# Pedal_LoopLEDS.net
KiCad netlist of a schematic drawn in Altium Designer
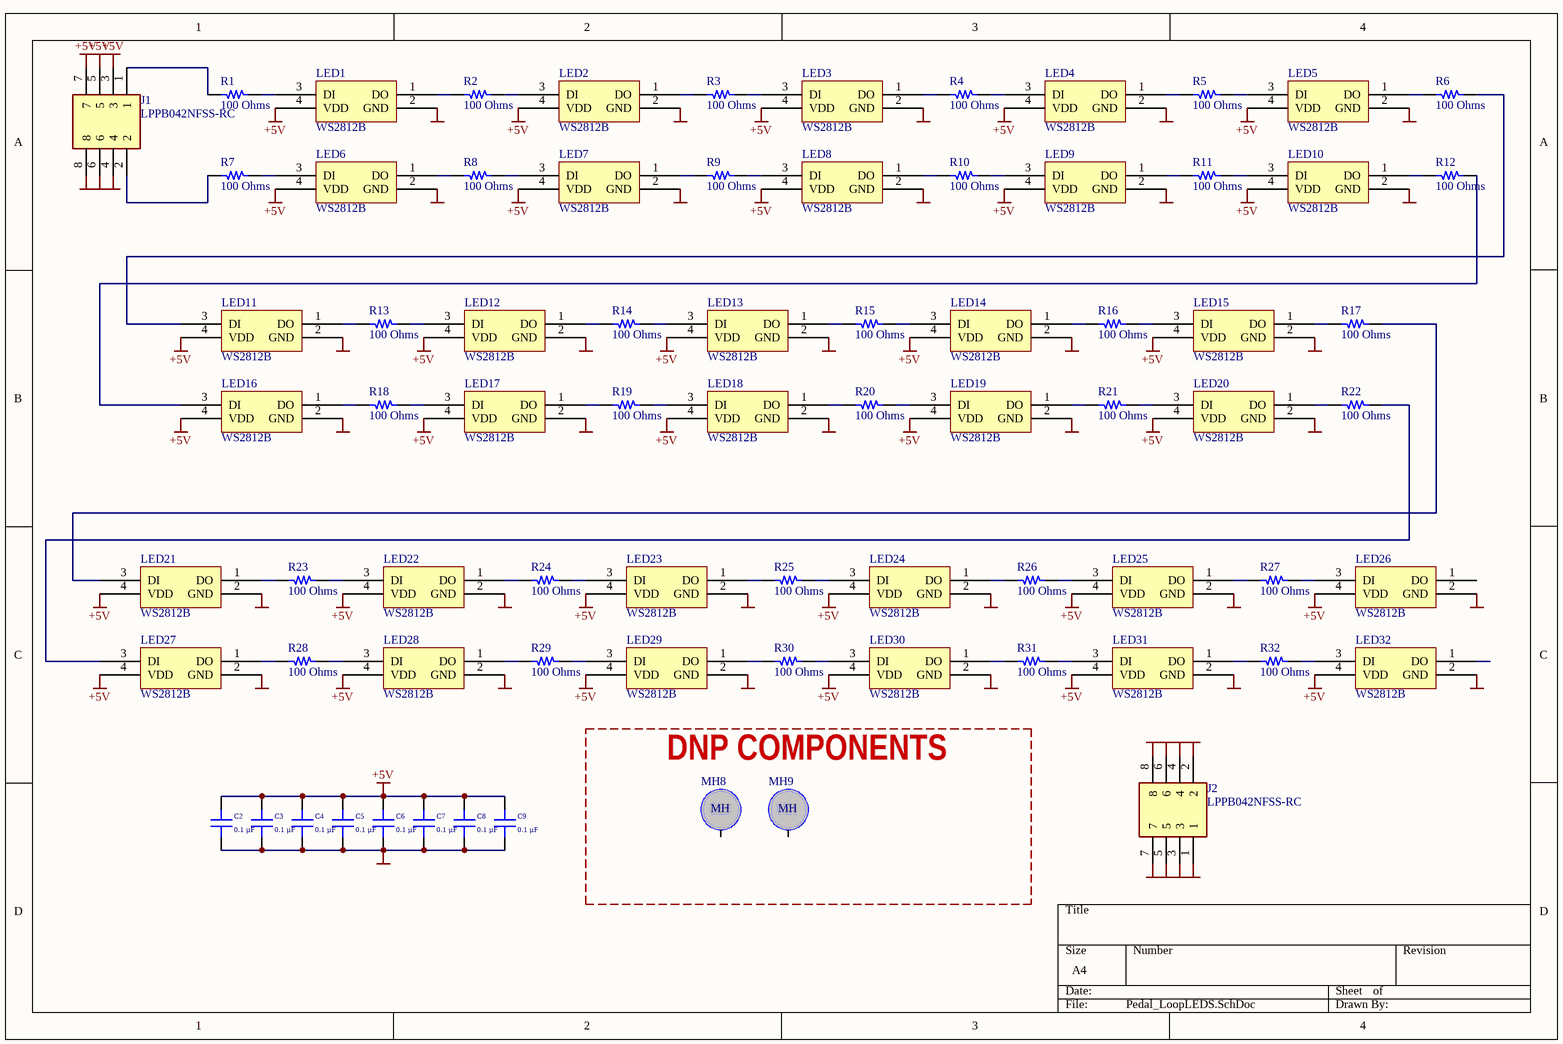
[diagram p0: Pedal_LoopLEDS.SchDoc]

(export (version "E")
  (design (tool "Eeschema 10.0.6"))
  (components
    (comp (ref "C2")
      (value "0.1 µF")
      (footprint "CAP 0603_1608")
      (description "CAP CER 0.1UF 50V X7R 0603")
      (fields (field (name "PART NUMBER") "C0603C104K5RAC7411") (field (name "MANUFACTURER") "KEMET"))
      (libsource (lib "Celestial Altium Library - altium_library") (part "Capacitor"))
    )
    (comp (ref "C3")
      (value "0.1 µF")
      (footprint "CAP 0603_1608")
      (description "CAP CER 0.1UF 50V X7R 0603")
      (fields (field (name "PART NUMBER") "C0603C104K5RAC7411") (field (name "MANUFACTURER") "KEMET"))
      (libsource (lib "Celestial Altium Library - altium_library") (part "Capacitor"))
    )
    (comp (ref "C4")
      (value "0.1 µF")
      (footprint "CAP 0603_1608")
      (description "CAP CER 0.1UF 50V X7R 0603")
      (fields (field (name "PART NUMBER") "C0603C104K5RAC7411") (field (name "MANUFACTURER") "KEMET"))
      (libsource (lib "Celestial Altium Library - altium_library") (part "Capacitor"))
    )
    (comp (ref "C5")
      (value "0.1 µF")
      (footprint "CAP 0603_1608")
      (description "CAP CER 0.1UF 50V X7R 0603")
      (fields (field (name "PART NUMBER") "C0603C104K5RAC7411") (field (name "MANUFACTURER") "KEMET"))
      (libsource (lib "Celestial Altium Library - altium_library") (part "Capacitor"))
    )
    (comp (ref "C6")
      (value "0.1 µF")
      (footprint "CAP 0603_1608")
      (description "CAP CER 0.1UF 50V X7R 0603")
      (fields (field (name "PART NUMBER") "C0603C104K5RAC7411") (field (name "MANUFACTURER") "KEMET"))
      (libsource (lib "Celestial Altium Library - altium_library") (part "Capacitor"))
    )
    (comp (ref "C7")
      (value "0.1 µF")
      (footprint "CAP 0603_1608")
      (description "CAP CER 0.1UF 50V X7R 0603")
      (fields (field (name "PART NUMBER") "C0603C104K5RAC7411") (field (name "MANUFACTURER") "KEMET"))
      (libsource (lib "Celestial Altium Library - altium_library") (part "Capacitor"))
    )
    (comp (ref "C8")
      (value "0.1 µF")
      (footprint "CAP 0603_1608")
      (description "CAP CER 0.1UF 50V X7R 0603")
      (fields (field (name "PART NUMBER") "C0603C104K5RAC7411") (field (name "MANUFACTURER") "KEMET"))
      (libsource (lib "Celestial Altium Library - altium_library") (part "Capacitor"))
    )
    (comp (ref "C9")
      (value "0.1 µF")
      (footprint "CAP 0603_1608")
      (description "CAP CER 0.1UF 50V X7R 0603")
      (fields (field (name "PART NUMBER") "C0603C104K5RAC7411") (field (name "MANUFACTURER") "KEMET"))
      (libsource (lib "Celestial Altium Library - altium_library") (part "Capacitor"))
    )
    (comp (ref "J1")
      (value "LPPB042NFSS-RC")
      (footprint "SamacSys:LPPB042NFSSRC")
      (description "Connector")
      (libsource (lib "") (part "LPPB042NFSS-RC_1"))
    )
    (comp (ref "J2")
      (value "LPPB042NFSS-RC")
      (footprint "SamacSys:LPPB042NFSSRC")
      (description "Connector")
      (libsource (lib "*") (part "LPPB042NFSS-RC"))
    )
    (comp (ref "LED1")
      (value "WS2812B")
      (footprint "ProtoStack_H750VBT:WS2812B_2.2x2mm")
      (description "Address LED")
      (libsource (lib "ProtoStack_H750VBT") (part "WS2812B"))
    )
    (comp (ref "LED2")
      (value "WS2812B")
      (footprint "ProtoStack_H750VBT:WS2812B_2.2x2mm")
      (description "Address LED")
      (libsource (lib "ProtoStack_H750VBT") (part "WS2812B"))
    )
    (comp (ref "LED3")
      (value "WS2812B")
      (footprint "ProtoStack_H750VBT:WS2812B_2.2x2mm")
      (description "Address LED")
      (libsource (lib "ProtoStack_H750VBT") (part "WS2812B"))
    )
    (comp (ref "LED4")
      (value "WS2812B")
      (footprint "ProtoStack_H750VBT:WS2812B_2.2x2mm")
      (description "Address LED")
      (libsource (lib "ProtoStack_H750VBT") (part "WS2812B"))
    )
    (comp (ref "LED5")
      (value "WS2812B")
      (footprint "ProtoStack_H750VBT:WS2812B_2.2x2mm")
      (description "Address LED")
      (libsource (lib "ProtoStack_H750VBT") (part "WS2812B"))
    )
    (comp (ref "LED6")
      (value "WS2812B")
      (footprint "ProtoStack_H750VBT:WS2812B_2.2x2mm")
      (description "Address LED")
      (libsource (lib "ProtoStack_H750VBT") (part "WS2812B"))
    )
    (comp (ref "LED7")
      (value "WS2812B")
      (footprint "ProtoStack_H750VBT:WS2812B_2.2x2mm")
      (description "Address LED")
      (libsource (lib "ProtoStack_H750VBT") (part "WS2812B"))
    )
    (comp (ref "LED8")
      (value "WS2812B")
      (footprint "ProtoStack_H750VBT:WS2812B_2.2x2mm")
      (description "Address LED")
      (libsource (lib "ProtoStack_H750VBT") (part "WS2812B"))
    )
    (comp (ref "LED9")
      (value "WS2812B")
      (footprint "ProtoStack_H750VBT:WS2812B_2.2x2mm")
      (description "Address LED")
      (libsource (lib "ProtoStack_H750VBT") (part "WS2812B"))
    )
    (comp (ref "LED10")
      (value "WS2812B")
      (footprint "ProtoStack_H750VBT:WS2812B_2.2x2mm")
      (description "Address LED")
      (libsource (lib "ProtoStack_H750VBT") (part "WS2812B"))
    )
    (comp (ref "LED11")
      (value "WS2812B")
      (footprint "ProtoStack_H750VBT:WS2812B_2.2x2mm")
      (description "Address LED")
      (libsource (lib "ProtoStack_H750VBT") (part "WS2812B"))
    )
    (comp (ref "LED12")
      (value "WS2812B")
      (footprint "ProtoStack_H750VBT:WS2812B_2.2x2mm")
      (description "Address LED")
      (libsource (lib "ProtoStack_H750VBT") (part "WS2812B"))
    )
    (comp (ref "LED13")
      (value "WS2812B")
      (footprint "ProtoStack_H750VBT:WS2812B_2.2x2mm")
      (description "Address LED")
      (libsource (lib "ProtoStack_H750VBT") (part "WS2812B"))
    )
    (comp (ref "LED14")
      (value "WS2812B")
      (footprint "ProtoStack_H750VBT:WS2812B_2.2x2mm")
      (description "Address LED")
      (libsource (lib "ProtoStack_H750VBT") (part "WS2812B"))
    )
    (comp (ref "LED15")
      (value "WS2812B")
      (footprint "ProtoStack_H750VBT:WS2812B_2.2x2mm")
      (description "Address LED")
      (libsource (lib "ProtoStack_H750VBT") (part "WS2812B"))
    )
    (comp (ref "LED16")
      (value "WS2812B")
      (footprint "ProtoStack_H750VBT:WS2812B_2.2x2mm")
      (description "Address LED")
      (libsource (lib "ProtoStack_H750VBT") (part "WS2812B"))
    )
    (comp (ref "LED17")
      (value "WS2812B")
      (footprint "ProtoStack_H750VBT:WS2812B_2.2x2mm")
      (description "Address LED")
      (libsource (lib "ProtoStack_H750VBT") (part "WS2812B"))
    )
    (comp (ref "LED18")
      (value "WS2812B")
      (footprint "ProtoStack_H750VBT:WS2812B_2.2x2mm")
      (description "Address LED")
      (libsource (lib "ProtoStack_H750VBT") (part "WS2812B"))
    )
    (comp (ref "LED19")
      (value "WS2812B")
      (footprint "ProtoStack_H750VBT:WS2812B_2.2x2mm")
      (description "Address LED")
      (libsource (lib "ProtoStack_H750VBT") (part "WS2812B"))
    )
    (comp (ref "LED20")
      (value "WS2812B")
      (footprint "ProtoStack_H750VBT:WS2812B_2.2x2mm")
      (description "Address LED")
      (libsource (lib "ProtoStack_H750VBT") (part "WS2812B"))
    )
    (comp (ref "LED21")
      (value "WS2812B")
      (footprint "ProtoStack_H750VBT:WS2812B_2.2x2mm")
      (description "Address LED")
      (libsource (lib "ProtoStack_H750VBT") (part "WS2812B"))
    )
    (comp (ref "LED22")
      (value "WS2812B")
      (footprint "ProtoStack_H750VBT:WS2812B_2.2x2mm")
      (description "Address LED")
      (libsource (lib "ProtoStack_H750VBT") (part "WS2812B"))
    )
    (comp (ref "LED23")
      (value "WS2812B")
      (footprint "ProtoStack_H750VBT:WS2812B_2.2x2mm")
      (description "Address LED")
      (libsource (lib "ProtoStack_H750VBT") (part "WS2812B"))
    )
    (comp (ref "LED24")
      (value "WS2812B")
      (footprint "ProtoStack_H750VBT:WS2812B_2.2x2mm")
      (description "Address LED")
      (libsource (lib "ProtoStack_H750VBT") (part "WS2812B"))
    )
    (comp (ref "LED25")
      (value "WS2812B")
      (footprint "ProtoStack_H750VBT:WS2812B_2.2x2mm")
      (description "Address LED")
      (libsource (lib "ProtoStack_H750VBT") (part "WS2812B"))
    )
    (comp (ref "LED26")
      (value "WS2812B")
      (footprint "ProtoStack_H750VBT:WS2812B_2.2x2mm")
      (description "Address LED")
      (libsource (lib "ProtoStack_H750VBT") (part "WS2812B"))
    )
    (comp (ref "LED27")
      (value "WS2812B")
      (footprint "ProtoStack_H750VBT:WS2812B_2.2x2mm")
      (description "Address LED")
      (libsource (lib "ProtoStack_H750VBT") (part "WS2812B"))
    )
    (comp (ref "LED28")
      (value "WS2812B")
      (footprint "ProtoStack_H750VBT:WS2812B_2.2x2mm")
      (description "Address LED")
      (libsource (lib "ProtoStack_H750VBT") (part "WS2812B"))
    )
    (comp (ref "LED29")
      (value "WS2812B")
      (footprint "ProtoStack_H750VBT:WS2812B_2.2x2mm")
      (description "Address LED")
      (libsource (lib "ProtoStack_H750VBT") (part "WS2812B"))
    )
    (comp (ref "LED30")
      (value "WS2812B")
      (footprint "ProtoStack_H750VBT:WS2812B_2.2x2mm")
      (description "Address LED")
      (libsource (lib "ProtoStack_H750VBT") (part "WS2812B"))
    )
    (comp (ref "LED31")
      (value "WS2812B")
      (footprint "ProtoStack_H750VBT:WS2812B_2.2x2mm")
      (description "Address LED")
      (libsource (lib "ProtoStack_H750VBT") (part "WS2812B"))
    )
    (comp (ref "LED32")
      (value "WS2812B")
      (footprint "ProtoStack_H750VBT:WS2812B_2.2x2mm")
      (description "Address LED")
      (libsource (lib "ProtoStack_H750VBT") (part "WS2812B"))
    )
    (comp (ref "MH8")
      (value "MountingHole")
      (footprint "ProtoStack_H750VBT:Hole_2.5mm")
      (libsource (lib "ProtoStack_H750VBT") (part "MountingHole"))
    )
    (comp (ref "MH9")
      (value "MountingHole")
      (footprint "ProtoStack_H750VBT:Hole_2.5mm")
      (libsource (lib "ProtoStack_H750VBT") (part "MountingHole"))
    )
    (comp (ref "R1")
      (value "100 Ohms")
      (footprint "RES 0402_1005")
      (description "RES SMD 100 OHM 1% 1/16W 0402")
      (fields (field (name "PART NUMBER") "CRCW0402100RFKEE") (field (name "MANUFACTURER") "Vishay Dale"))
      (libsource (lib "Celestial Altium Library - altium_library") (part "Resistor"))
    )
    (comp (ref "R2")
      (value "100 Ohms")
      (footprint "RES 0402_1005")
      (description "RES SMD 100 OHM 1% 1/16W 0402")
      (fields (field (name "PART NUMBER") "CRCW0402100RFKEE") (field (name "MANUFACTURER") "Vishay Dale"))
      (libsource (lib "Celestial Altium Library - altium_library") (part "Resistor"))
    )
    (comp (ref "R3")
      (value "100 Ohms")
      (footprint "RES 0402_1005")
      (description "RES SMD 100 OHM 1% 1/16W 0402")
      (fields (field (name "PART NUMBER") "CRCW0402100RFKEE") (field (name "MANUFACTURER") "Vishay Dale"))
      (libsource (lib "Celestial Altium Library - altium_library") (part "Resistor"))
    )
    (comp (ref "R4")
      (value "100 Ohms")
      (footprint "RES 0402_1005")
      (description "RES SMD 100 OHM 1% 1/16W 0402")
      (fields (field (name "PART NUMBER") "CRCW0402100RFKEE") (field (name "MANUFACTURER") "Vishay Dale"))
      (libsource (lib "Celestial Altium Library - altium_library") (part "Resistor"))
    )
    (comp (ref "R5")
      (value "100 Ohms")
      (footprint "RES 0402_1005")
      (description "RES SMD 100 OHM 1% 1/16W 0402")
      (fields (field (name "PART NUMBER") "CRCW0402100RFKEE") (field (name "MANUFACTURER") "Vishay Dale"))
      (libsource (lib "Celestial Altium Library - altium_library") (part "Resistor"))
    )
    (comp (ref "R6")
      (value "100 Ohms")
      (footprint "RES 0402_1005")
      (description "RES SMD 100 OHM 1% 1/16W 0402")
      (fields (field (name "PART NUMBER") "CRCW0402100RFKEE") (field (name "MANUFACTURER") "Vishay Dale"))
      (libsource (lib "Celestial Altium Library - altium_library") (part "Resistor"))
    )
    (comp (ref "R7")
      (value "100 Ohms")
      (footprint "RES 0402_1005")
      (description "RES SMD 100 OHM 1% 1/16W 0402")
      (fields (field (name "PART NUMBER") "CRCW0402100RFKEE") (field (name "MANUFACTURER") "Vishay Dale"))
      (libsource (lib "Celestial Altium Library - altium_library") (part "Resistor"))
    )
    (comp (ref "R8")
      (value "100 Ohms")
      (footprint "RES 0402_1005")
      (description "RES SMD 100 OHM 1% 1/16W 0402")
      (fields (field (name "PART NUMBER") "CRCW0402100RFKEE") (field (name "MANUFACTURER") "Vishay Dale"))
      (libsource (lib "Celestial Altium Library - altium_library") (part "Resistor"))
    )
    (comp (ref "R9")
      (value "100 Ohms")
      (footprint "RES 0402_1005")
      (description "RES SMD 100 OHM 1% 1/16W 0402")
      (fields (field (name "PART NUMBER") "CRCW0402100RFKEE") (field (name "MANUFACTURER") "Vishay Dale"))
      (libsource (lib "Celestial Altium Library - altium_library") (part "Resistor"))
    )
    (comp (ref "R10")
      (value "100 Ohms")
      (footprint "RES 0402_1005")
      (description "RES SMD 100 OHM 1% 1/16W 0402")
      (fields (field (name "PART NUMBER") "CRCW0402100RFKEE") (field (name "MANUFACTURER") "Vishay Dale"))
      (libsource (lib "Celestial Altium Library - altium_library") (part "Resistor"))
    )
    (comp (ref "R11")
      (value "100 Ohms")
      (footprint "RES 0402_1005")
      (description "RES SMD 100 OHM 1% 1/16W 0402")
      (fields (field (name "PART NUMBER") "CRCW0402100RFKEE") (field (name "MANUFACTURER") "Vishay Dale"))
      (libsource (lib "Celestial Altium Library - altium_library") (part "Resistor"))
    )
    (comp (ref "R12")
      (value "100 Ohms")
      (footprint "RES 0402_1005")
      (description "RES SMD 100 OHM 1% 1/16W 0402")
      (fields (field (name "PART NUMBER") "CRCW0402100RFKEE") (field (name "MANUFACTURER") "Vishay Dale"))
      (libsource (lib "Celestial Altium Library - altium_library") (part "Resistor"))
    )
    (comp (ref "R13")
      (value "100 Ohms")
      (footprint "RES 0402_1005")
      (description "RES SMD 100 OHM 1% 1/16W 0402")
      (fields (field (name "PART NUMBER") "CRCW0402100RFKEE") (field (name "MANUFACTURER") "Vishay Dale"))
      (libsource (lib "Celestial Altium Library - altium_library") (part "Resistor"))
    )
    (comp (ref "R14")
      (value "100 Ohms")
      (footprint "RES 0402_1005")
      (description "RES SMD 100 OHM 1% 1/16W 0402")
      (fields (field (name "PART NUMBER") "CRCW0402100RFKEE") (field (name "MANUFACTURER") "Vishay Dale"))
      (libsource (lib "Celestial Altium Library - altium_library") (part "Resistor"))
    )
    (comp (ref "R15")
      (value "100 Ohms")
      (footprint "RES 0402_1005")
      (description "RES SMD 100 OHM 1% 1/16W 0402")
      (fields (field (name "PART NUMBER") "CRCW0402100RFKEE") (field (name "MANUFACTURER") "Vishay Dale"))
      (libsource (lib "Celestial Altium Library - altium_library") (part "Resistor"))
    )
    (comp (ref "R16")
      (value "100 Ohms")
      (footprint "RES 0402_1005")
      (description "RES SMD 100 OHM 1% 1/16W 0402")
      (fields (field (name "PART NUMBER") "CRCW0402100RFKEE") (field (name "MANUFACTURER") "Vishay Dale"))
      (libsource (lib "Celestial Altium Library - altium_library") (part "Resistor"))
    )
    (comp (ref "R17")
      (value "100 Ohms")
      (footprint "RES 0402_1005")
      (description "RES SMD 100 OHM 1% 1/16W 0402")
      (fields (field (name "PART NUMBER") "CRCW0402100RFKEE") (field (name "MANUFACTURER") "Vishay Dale"))
      (libsource (lib "Celestial Altium Library - altium_library") (part "Resistor"))
    )
    (comp (ref "R18")
      (value "100 Ohms")
      (footprint "RES 0402_1005")
      (description "RES SMD 100 OHM 1% 1/16W 0402")
      (fields (field (name "PART NUMBER") "CRCW0402100RFKEE") (field (name "MANUFACTURER") "Vishay Dale"))
      (libsource (lib "Celestial Altium Library - altium_library") (part "Resistor"))
    )
    (comp (ref "R19")
      (value "100 Ohms")
      (footprint "RES 0402_1005")
      (description "RES SMD 100 OHM 1% 1/16W 0402")
      (fields (field (name "PART NUMBER") "CRCW0402100RFKEE") (field (name "MANUFACTURER") "Vishay Dale"))
      (libsource (lib "Celestial Altium Library - altium_library") (part "Resistor"))
    )
    (comp (ref "R20")
      (value "100 Ohms")
      (footprint "RES 0402_1005")
      (description "RES SMD 100 OHM 1% 1/16W 0402")
      (fields (field (name "PART NUMBER") "CRCW0402100RFKEE") (field (name "MANUFACTURER") "Vishay Dale"))
      (libsource (lib "Celestial Altium Library - altium_library") (part "Resistor"))
    )
    (comp (ref "R21")
      (value "100 Ohms")
      (footprint "RES 0402_1005")
      (description "RES SMD 100 OHM 1% 1/16W 0402")
      (fields (field (name "PART NUMBER") "CRCW0402100RFKEE") (field (name "MANUFACTURER") "Vishay Dale"))
      (libsource (lib "Celestial Altium Library - altium_library") (part "Resistor"))
    )
    (comp (ref "R22")
      (value "100 Ohms")
      (footprint "RES 0402_1005")
      (description "RES SMD 100 OHM 1% 1/16W 0402")
      (fields (field (name "PART NUMBER") "CRCW0402100RFKEE") (field (name "MANUFACTURER") "Vishay Dale"))
      (libsource (lib "Celestial Altium Library - altium_library") (part "Resistor"))
    )
    (comp (ref "R23")
      (value "100 Ohms")
      (footprint "RES 0402_1005")
      (description "RES SMD 100 OHM 1% 1/16W 0402")
      (fields (field (name "PART NUMBER") "CRCW0402100RFKEE") (field (name "MANUFACTURER") "Vishay Dale"))
      (libsource (lib "Celestial Altium Library - altium_library") (part "Resistor"))
    )
    (comp (ref "R24")
      (value "100 Ohms")
      (footprint "RES 0402_1005")
      (description "RES SMD 100 OHM 1% 1/16W 0402")
      (fields (field (name "PART NUMBER") "CRCW0402100RFKEE") (field (name "MANUFACTURER") "Vishay Dale"))
      (libsource (lib "Celestial Altium Library - altium_library") (part "Resistor"))
    )
    (comp (ref "R25")
      (value "100 Ohms")
      (footprint "RES 0402_1005")
      (description "RES SMD 100 OHM 1% 1/16W 0402")
      (fields (field (name "PART NUMBER") "CRCW0402100RFKEE") (field (name "MANUFACTURER") "Vishay Dale"))
      (libsource (lib "Celestial Altium Library - altium_library") (part "Resistor"))
    )
    (comp (ref "R26")
      (value "100 Ohms")
      (footprint "RES 0402_1005")
      (description "RES SMD 100 OHM 1% 1/16W 0402")
      (fields (field (name "PART NUMBER") "CRCW0402100RFKEE") (field (name "MANUFACTURER") "Vishay Dale"))
      (libsource (lib "Celestial Altium Library - altium_library") (part "Resistor"))
    )
    (comp (ref "R27")
      (value "100 Ohms")
      (footprint "RES 0402_1005")
      (description "RES SMD 100 OHM 1% 1/16W 0402")
      (fields (field (name "PART NUMBER") "CRCW0402100RFKEE") (field (name "MANUFACTURER") "Vishay Dale"))
      (libsource (lib "Celestial Altium Library - altium_library") (part "Resistor"))
    )
    (comp (ref "R28")
      (value "100 Ohms")
      (footprint "RES 0402_1005")
      (description "RES SMD 100 OHM 1% 1/16W 0402")
      (fields (field (name "PART NUMBER") "CRCW0402100RFKEE") (field (name "MANUFACTURER") "Vishay Dale"))
      (libsource (lib "Celestial Altium Library - altium_library") (part "Resistor"))
    )
    (comp (ref "R29")
      (value "100 Ohms")
      (footprint "RES 0402_1005")
      (description "RES SMD 100 OHM 1% 1/16W 0402")
      (fields (field (name "PART NUMBER") "CRCW0402100RFKEE") (field (name "MANUFACTURER") "Vishay Dale"))
      (libsource (lib "Celestial Altium Library - altium_library") (part "Resistor"))
    )
    (comp (ref "R30")
      (value "100 Ohms")
      (footprint "RES 0402_1005")
      (description "RES SMD 100 OHM 1% 1/16W 0402")
      (fields (field (name "PART NUMBER") "CRCW0402100RFKEE") (field (name "MANUFACTURER") "Vishay Dale"))
      (libsource (lib "Celestial Altium Library - altium_library") (part "Resistor"))
    )
    (comp (ref "R31")
      (value "100 Ohms")
      (footprint "RES 0402_1005")
      (description "RES SMD 100 OHM 1% 1/16W 0402")
      (fields (field (name "PART NUMBER") "CRCW0402100RFKEE") (field (name "MANUFACTURER") "Vishay Dale"))
      (libsource (lib "Celestial Altium Library - altium_library") (part "Resistor"))
    )
    (comp (ref "R32")
      (value "100 Ohms")
      (footprint "RES 0402_1005")
      (description "RES SMD 100 OHM 1% 1/16W 0402")
      (fields (field (name "PART NUMBER") "CRCW0402100RFKEE") (field (name "MANUFACTURER") "Vishay Dale"))
      (libsource (lib "Celestial Altium Library - altium_library") (part "Resistor"))
    )
  )
  (nets
    (net (code "1") (name "+5V") (class "Default")
      (node (ref "C2") (pin "2") (pinfunction "2_2") (pintype "passive"))
      (node (ref "C3") (pin "2") (pinfunction "2_2") (pintype "passive"))
      (node (ref "C4") (pin "2") (pinfunction "2_2") (pintype "passive"))
      (node (ref "C5") (pin "2") (pinfunction "2_2") (pintype "passive"))
      (node (ref "C6") (pin "2") (pinfunction "2_2") (pintype "passive"))
      (node (ref "C7") (pin "2") (pinfunction "2_2") (pintype "passive"))
      (node (ref "C8") (pin "2") (pinfunction "2_2") (pintype "passive"))
      (node (ref "C9") (pin "2") (pinfunction "2_2") (pintype "passive"))
      (node (ref "J1") (pin "3") (pinfunction "3_3") (pintype "passive"))
      (node (ref "J1") (pin "5") (pinfunction "5_5") (pintype "passive"))
      (node (ref "J1") (pin "7") (pinfunction "7_7") (pintype "passive"))
      (node (ref "LED1") (pin "4") (pinfunction "VDD_4") (pintype "passive"))
      (node (ref "LED10") (pin "4") (pinfunction "VDD_4") (pintype "passive"))
      (node (ref "LED11") (pin "4") (pinfunction "VDD_4") (pintype "passive"))
      (node (ref "LED12") (pin "4") (pinfunction "VDD_4") (pintype "passive"))
      (node (ref "LED13") (pin "4") (pinfunction "VDD_4") (pintype "passive"))
      (node (ref "LED14") (pin "4") (pinfunction "VDD_4") (pintype "passive"))
      (node (ref "LED15") (pin "4") (pinfunction "VDD_4") (pintype "passive"))
      (node (ref "LED16") (pin "4") (pinfunction "VDD_4") (pintype "passive"))
      (node (ref "LED17") (pin "4") (pinfunction "VDD_4") (pintype "passive"))
      (node (ref "LED18") (pin "4") (pinfunction "VDD_4") (pintype "passive"))
      (node (ref "LED19") (pin "4") (pinfunction "VDD_4") (pintype "passive"))
      (node (ref "LED2") (pin "4") (pinfunction "VDD_4") (pintype "passive"))
      (node (ref "LED20") (pin "4") (pinfunction "VDD_4") (pintype "passive"))
      (node (ref "LED21") (pin "4") (pinfunction "VDD_4") (pintype "passive"))
      (node (ref "LED22") (pin "4") (pinfunction "VDD_4") (pintype "passive"))
      (node (ref "LED23") (pin "4") (pinfunction "VDD_4") (pintype "passive"))
      (node (ref "LED24") (pin "4") (pinfunction "VDD_4") (pintype "passive"))
      (node (ref "LED25") (pin "4") (pinfunction "VDD_4") (pintype "passive"))
      (node (ref "LED26") (pin "4") (pinfunction "VDD_4") (pintype "passive"))
      (node (ref "LED27") (pin "4") (pinfunction "VDD_4") (pintype "passive"))
      (node (ref "LED28") (pin "4") (pinfunction "VDD_4") (pintype "passive"))
      (node (ref "LED29") (pin "4") (pinfunction "VDD_4") (pintype "passive"))
      (node (ref "LED3") (pin "4") (pinfunction "VDD_4") (pintype "passive"))
      (node (ref "LED30") (pin "4") (pinfunction "VDD_4") (pintype "passive"))
      (node (ref "LED31") (pin "4") (pinfunction "VDD_4") (pintype "passive"))
      (node (ref "LED32") (pin "4") (pinfunction "VDD_4") (pintype "passive"))
      (node (ref "LED4") (pin "4") (pinfunction "VDD_4") (pintype "passive"))
      (node (ref "LED5") (pin "4") (pinfunction "VDD_4") (pintype "passive"))
      (node (ref "LED6") (pin "4") (pinfunction "VDD_4") (pintype "passive"))
      (node (ref "LED7") (pin "4") (pinfunction "VDD_4") (pintype "passive"))
      (node (ref "LED8") (pin "4") (pinfunction "VDD_4") (pintype "passive"))
      (node (ref "LED9") (pin "4") (pinfunction "VDD_4") (pintype "passive"))
    )
    (net (code "2") (name "GND") (class "Default")
      (node (ref "C2") (pin "1") (pinfunction "1_1") (pintype "passive"))
      (node (ref "C3") (pin "1") (pinfunction "1_1") (pintype "passive"))
      (node (ref "C4") (pin "1") (pinfunction "1_1") (pintype "passive"))
      (node (ref "C5") (pin "1") (pinfunction "1_1") (pintype "passive"))
      (node (ref "C6") (pin "1") (pinfunction "1_1") (pintype "passive"))
      (node (ref "C7") (pin "1") (pinfunction "1_1") (pintype "passive"))
      (node (ref "C8") (pin "1") (pinfunction "1_1") (pintype "passive"))
      (node (ref "C9") (pin "1") (pinfunction "1_1") (pintype "passive"))
      (node (ref "J1") (pin "4") (pinfunction "4_4") (pintype "passive"))
      (node (ref "J1") (pin "6") (pinfunction "6_6") (pintype "passive"))
      (node (ref "J1") (pin "8") (pinfunction "8_8") (pintype "passive"))
      (node (ref "J2") (pin "1") (pinfunction "1_1") (pintype "passive"))
      (node (ref "J2") (pin "2") (pinfunction "2_2") (pintype "passive"))
      (node (ref "J2") (pin "3") (pinfunction "3_3") (pintype "passive"))
      (node (ref "J2") (pin "4") (pinfunction "4_4") (pintype "passive"))
      (node (ref "J2") (pin "5") (pinfunction "5_5") (pintype "passive"))
      (node (ref "J2") (pin "6") (pinfunction "6_6") (pintype "passive"))
      (node (ref "J2") (pin "7") (pinfunction "7_7") (pintype "passive"))
      (node (ref "J2") (pin "8") (pinfunction "8_8") (pintype "passive"))
      (node (ref "LED1") (pin "2") (pinfunction "GND_2") (pintype "passive"))
      (node (ref "LED10") (pin "2") (pinfunction "GND_2") (pintype "passive"))
      (node (ref "LED11") (pin "2") (pinfunction "GND_2") (pintype "passive"))
      (node (ref "LED12") (pin "2") (pinfunction "GND_2") (pintype "passive"))
      (node (ref "LED13") (pin "2") (pinfunction "GND_2") (pintype "passive"))
      (node (ref "LED14") (pin "2") (pinfunction "GND_2") (pintype "passive"))
      (node (ref "LED15") (pin "2") (pinfunction "GND_2") (pintype "passive"))
      (node (ref "LED16") (pin "2") (pinfunction "GND_2") (pintype "passive"))
      (node (ref "LED17") (pin "2") (pinfunction "GND_2") (pintype "passive"))
      (node (ref "LED18") (pin "2") (pinfunction "GND_2") (pintype "passive"))
      (node (ref "LED19") (pin "2") (pinfunction "GND_2") (pintype "passive"))
      (node (ref "LED2") (pin "2") (pinfunction "GND_2") (pintype "passive"))
      (node (ref "LED20") (pin "2") (pinfunction "GND_2") (pintype "passive"))
      (node (ref "LED21") (pin "2") (pinfunction "GND_2") (pintype "passive"))
      (node (ref "LED22") (pin "2") (pinfunction "GND_2") (pintype "passive"))
      (node (ref "LED23") (pin "2") (pinfunction "GND_2") (pintype "passive"))
      (node (ref "LED24") (pin "2") (pinfunction "GND_2") (pintype "passive"))
      (node (ref "LED25") (pin "2") (pinfunction "GND_2") (pintype "passive"))
      (node (ref "LED26") (pin "2") (pinfunction "GND_2") (pintype "passive"))
      (node (ref "LED27") (pin "2") (pinfunction "GND_2") (pintype "passive"))
      (node (ref "LED28") (pin "2") (pinfunction "GND_2") (pintype "passive"))
      (node (ref "LED29") (pin "2") (pinfunction "GND_2") (pintype "passive"))
      (node (ref "LED3") (pin "2") (pinfunction "GND_2") (pintype "passive"))
      (node (ref "LED30") (pin "2") (pinfunction "GND_2") (pintype "passive"))
      (node (ref "LED31") (pin "2") (pinfunction "GND_2") (pintype "passive"))
      (node (ref "LED32") (pin "2") (pinfunction "GND_2") (pintype "passive"))
      (node (ref "LED4") (pin "2") (pinfunction "GND_2") (pintype "passive"))
      (node (ref "LED5") (pin "2") (pinfunction "GND_2") (pintype "passive"))
      (node (ref "LED6") (pin "2") (pinfunction "GND_2") (pintype "passive"))
      (node (ref "LED7") (pin "2") (pinfunction "GND_2") (pintype "passive"))
      (node (ref "LED8") (pin "2") (pinfunction "GND_2") (pintype "passive"))
      (node (ref "LED9") (pin "2") (pinfunction "GND_2") (pintype "passive"))
    )
    (net (code "3") (name "Net-(J1-Pad1)") (class "Default")
      (node (ref "J1") (pin "1") (pinfunction "1_1") (pintype "passive"))
      (node (ref "R1") (pin "2") (pinfunction "2_2") (pintype "passive"))
    )
    (net (code "4") (name "Net-(J1-Pad2)") (class "Default")
      (node (ref "J1") (pin "2") (pinfunction "2_2") (pintype "passive"))
      (node (ref "R7") (pin "2") (pinfunction "2_2") (pintype "passive"))
    )
    (net (code "5") (name "Net-(LED1-DI)") (class "Default")
      (node (ref "LED1") (pin "3") (pinfunction "DI_3") (pintype "passive"))
      (node (ref "R1") (pin "1") (pinfunction "1_1") (pintype "passive"))
    )
    (net (code "6") (name "Net-(LED1-DO)") (class "Default")
      (node (ref "LED1") (pin "1") (pinfunction "DO_1") (pintype "passive"))
      (node (ref "R2") (pin "2") (pinfunction "2_2") (pintype "passive"))
    )
    (net (code "7") (name "Net-(LED2-DI)") (class "Default")
      (node (ref "LED2") (pin "3") (pinfunction "DI_3") (pintype "passive"))
      (node (ref "R2") (pin "1") (pinfunction "1_1") (pintype "passive"))
    )
    (net (code "8") (name "Net-(LED2-DO)") (class "Default")
      (node (ref "LED2") (pin "1") (pinfunction "DO_1") (pintype "passive"))
      (node (ref "R3") (pin "2") (pinfunction "2_2") (pintype "passive"))
    )
    (net (code "9") (name "Net-(LED3-DI)") (class "Default")
      (node (ref "LED3") (pin "3") (pinfunction "DI_3") (pintype "passive"))
      (node (ref "R3") (pin "1") (pinfunction "1_1") (pintype "passive"))
    )
    (net (code "10") (name "Net-(LED3-DO)") (class "Default")
      (node (ref "LED3") (pin "1") (pinfunction "DO_1") (pintype "passive"))
      (node (ref "R4") (pin "2") (pinfunction "2_2") (pintype "passive"))
    )
    (net (code "11") (name "Net-(LED4-DI)") (class "Default")
      (node (ref "LED4") (pin "3") (pinfunction "DI_3") (pintype "passive"))
      (node (ref "R4") (pin "1") (pinfunction "1_1") (pintype "passive"))
    )
    (net (code "12") (name "Net-(LED4-DO)") (class "Default")
      (node (ref "LED4") (pin "1") (pinfunction "DO_1") (pintype "passive"))
      (node (ref "R5") (pin "2") (pinfunction "2_2") (pintype "passive"))
    )
    (net (code "13") (name "Net-(LED5-DI)") (class "Default")
      (node (ref "LED5") (pin "3") (pinfunction "DI_3") (pintype "passive"))
      (node (ref "R5") (pin "1") (pinfunction "1_1") (pintype "passive"))
    )
    (net (code "14") (name "Net-(LED5-DO)") (class "Default")
      (node (ref "LED5") (pin "1") (pinfunction "DO_1") (pintype "passive"))
      (node (ref "R6") (pin "2") (pinfunction "2_2") (pintype "passive"))
    )
    (net (code "15") (name "Net-(LED6-DI)") (class "Default")
      (node (ref "LED6") (pin "3") (pinfunction "DI_3") (pintype "passive"))
      (node (ref "R7") (pin "1") (pinfunction "1_1") (pintype "passive"))
    )
    (net (code "16") (name "Net-(LED6-DO)") (class "Default")
      (node (ref "LED6") (pin "1") (pinfunction "DO_1") (pintype "passive"))
      (node (ref "R8") (pin "2") (pinfunction "2_2") (pintype "passive"))
    )
    (net (code "17") (name "Net-(LED7-DI)") (class "Default")
      (node (ref "LED7") (pin "3") (pinfunction "DI_3") (pintype "passive"))
      (node (ref "R8") (pin "1") (pinfunction "1_1") (pintype "passive"))
    )
    (net (code "18") (name "Net-(LED7-DO)") (class "Default")
      (node (ref "LED7") (pin "1") (pinfunction "DO_1") (pintype "passive"))
      (node (ref "R9") (pin "2") (pinfunction "2_2") (pintype "passive"))
    )
    (net (code "19") (name "Net-(LED8-DI)") (class "Default")
      (node (ref "LED8") (pin "3") (pinfunction "DI_3") (pintype "passive"))
      (node (ref "R9") (pin "1") (pinfunction "1_1") (pintype "passive"))
    )
    (net (code "20") (name "Net-(LED8-DO)") (class "Default")
      (node (ref "LED8") (pin "1") (pinfunction "DO_1") (pintype "passive"))
      (node (ref "R10") (pin "2") (pinfunction "2_2") (pintype "passive"))
    )
    (net (code "21") (name "Net-(LED9-DI)") (class "Default")
      (node (ref "LED9") (pin "3") (pinfunction "DI_3") (pintype "passive"))
      (node (ref "R10") (pin "1") (pinfunction "1_1") (pintype "passive"))
    )
    (net (code "22") (name "Net-(LED9-DO)") (class "Default")
      (node (ref "LED9") (pin "1") (pinfunction "DO_1") (pintype "passive"))
      (node (ref "R11") (pin "2") (pinfunction "2_2") (pintype "passive"))
    )
    (net (code "23") (name "Net-(LED10-DI)") (class "Default")
      (node (ref "LED10") (pin "3") (pinfunction "DI_3") (pintype "passive"))
      (node (ref "R11") (pin "1") (pinfunction "1_1") (pintype "passive"))
    )
    (net (code "24") (name "Net-(LED10-DO)") (class "Default")
      (node (ref "LED10") (pin "1") (pinfunction "DO_1") (pintype "passive"))
      (node (ref "R12") (pin "2") (pinfunction "2_2") (pintype "passive"))
    )
    (net (code "25") (name "Net-(LED11-DI)") (class "Default")
      (node (ref "LED11") (pin "3") (pinfunction "DI_3") (pintype "passive"))
      (node (ref "R6") (pin "1") (pinfunction "1_1") (pintype "passive"))
    )
    (net (code "26") (name "Net-(LED11-DO)") (class "Default")
      (node (ref "LED11") (pin "1") (pinfunction "DO_1") (pintype "passive"))
      (node (ref "R13") (pin "2") (pinfunction "2_2") (pintype "passive"))
    )
    (net (code "27") (name "Net-(LED12-DI)") (class "Default")
      (node (ref "LED12") (pin "3") (pinfunction "DI_3") (pintype "passive"))
      (node (ref "R13") (pin "1") (pinfunction "1_1") (pintype "passive"))
    )
    (net (code "28") (name "Net-(LED12-DO)") (class "Default")
      (node (ref "LED12") (pin "1") (pinfunction "DO_1") (pintype "passive"))
      (node (ref "R14") (pin "2") (pinfunction "2_2") (pintype "passive"))
    )
    (net (code "29") (name "Net-(LED13-DI)") (class "Default")
      (node (ref "LED13") (pin "3") (pinfunction "DI_3") (pintype "passive"))
      (node (ref "R14") (pin "1") (pinfunction "1_1") (pintype "passive"))
    )
    (net (code "30") (name "Net-(LED13-DO)") (class "Default")
      (node (ref "LED13") (pin "1") (pinfunction "DO_1") (pintype "passive"))
      (node (ref "R15") (pin "2") (pinfunction "2_2") (pintype "passive"))
    )
    (net (code "31") (name "Net-(LED14-DI)") (class "Default")
      (node (ref "LED14") (pin "3") (pinfunction "DI_3") (pintype "passive"))
      (node (ref "R15") (pin "1") (pinfunction "1_1") (pintype "passive"))
    )
    (net (code "32") (name "Net-(LED14-DO)") (class "Default")
      (node (ref "LED14") (pin "1") (pinfunction "DO_1") (pintype "passive"))
      (node (ref "R16") (pin "2") (pinfunction "2_2") (pintype "passive"))
    )
    (net (code "33") (name "Net-(LED15-DI)") (class "Default")
      (node (ref "LED15") (pin "3") (pinfunction "DI_3") (pintype "passive"))
      (node (ref "R16") (pin "1") (pinfunction "1_1") (pintype "passive"))
    )
    (net (code "34") (name "Net-(LED15-DO)") (class "Default")
      (node (ref "LED15") (pin "1") (pinfunction "DO_1") (pintype "passive"))
      (node (ref "R17") (pin "2") (pinfunction "2_2") (pintype "passive"))
    )
    (net (code "35") (name "Net-(LED16-DI)") (class "Default")
      (node (ref "LED16") (pin "3") (pinfunction "DI_3") (pintype "passive"))
      (node (ref "R12") (pin "1") (pinfunction "1_1") (pintype "passive"))
    )
    (net (code "36") (name "Net-(LED16-DO)") (class "Default")
      (node (ref "LED16") (pin "1") (pinfunction "DO_1") (pintype "passive"))
      (node (ref "R18") (pin "2") (pinfunction "2_2") (pintype "passive"))
    )
    (net (code "37") (name "Net-(LED17-DI)") (class "Default")
      (node (ref "LED17") (pin "3") (pinfunction "DI_3") (pintype "passive"))
      (node (ref "R18") (pin "1") (pinfunction "1_1") (pintype "passive"))
    )
    (net (code "38") (name "Net-(LED17-DO)") (class "Default")
      (node (ref "LED17") (pin "1") (pinfunction "DO_1") (pintype "passive"))
      (node (ref "R19") (pin "2") (pinfunction "2_2") (pintype "passive"))
    )
    (net (code "39") (name "Net-(LED18-DI)") (class "Default")
      (node (ref "LED18") (pin "3") (pinfunction "DI_3") (pintype "passive"))
      (node (ref "R19") (pin "1") (pinfunction "1_1") (pintype "passive"))
    )
    (net (code "40") (name "Net-(LED18-DO)") (class "Default")
      (node (ref "LED18") (pin "1") (pinfunction "DO_1") (pintype "passive"))
      (node (ref "R20") (pin "2") (pinfunction "2_2") (pintype "passive"))
    )
    (net (code "41") (name "Net-(LED19-DI)") (class "Default")
      (node (ref "LED19") (pin "3") (pinfunction "DI_3") (pintype "passive"))
      (node (ref "R20") (pin "1") (pinfunction "1_1") (pintype "passive"))
    )
    (net (code "42") (name "Net-(LED19-DO)") (class "Default")
      (node (ref "LED19") (pin "1") (pinfunction "DO_1") (pintype "passive"))
      (node (ref "R21") (pin "2") (pinfunction "2_2") (pintype "passive"))
    )
    (net (code "43") (name "Net-(LED20-DI)") (class "Default")
      (node (ref "LED20") (pin "3") (pinfunction "DI_3") (pintype "passive"))
      (node (ref "R21") (pin "1") (pinfunction "1_1") (pintype "passive"))
    )
    (net (code "44") (name "Net-(LED20-DO)") (class "Default")
      (node (ref "LED20") (pin "1") (pinfunction "DO_1") (pintype "passive"))
      (node (ref "R22") (pin "2") (pinfunction "2_2") (pintype "passive"))
    )
    (net (code "45") (name "Net-(LED21-DI)") (class "Default")
      (node (ref "LED21") (pin "3") (pinfunction "DI_3") (pintype "passive"))
      (node (ref "R17") (pin "1") (pinfunction "1_1") (pintype "passive"))
    )
    (net (code "46") (name "Net-(LED21-DO)") (class "Default")
      (node (ref "LED21") (pin "1") (pinfunction "DO_1") (pintype "passive"))
      (node (ref "R23") (pin "2") (pinfunction "2_2") (pintype "passive"))
    )
    (net (code "47") (name "Net-(LED22-DI)") (class "Default")
      (node (ref "LED22") (pin "3") (pinfunction "DI_3") (pintype "passive"))
      (node (ref "R23") (pin "1") (pinfunction "1_1") (pintype "passive"))
    )
    (net (code "48") (name "Net-(LED22-DO)") (class "Default")
      (node (ref "LED22") (pin "1") (pinfunction "DO_1") (pintype "passive"))
      (node (ref "R24") (pin "2") (pinfunction "2_2") (pintype "passive"))
    )
    (net (code "49") (name "Net-(LED23-DI)") (class "Default")
      (node (ref "LED23") (pin "3") (pinfunction "DI_3") (pintype "passive"))
      (node (ref "R24") (pin "1") (pinfunction "1_1") (pintype "passive"))
    )
    (net (code "50") (name "Net-(LED23-DO)") (class "Default")
      (node (ref "LED23") (pin "1") (pinfunction "DO_1") (pintype "passive"))
      (node (ref "R25") (pin "2") (pinfunction "2_2") (pintype "passive"))
    )
    (net (code "51") (name "Net-(LED24-DI)") (class "Default")
      (node (ref "LED24") (pin "3") (pinfunction "DI_3") (pintype "passive"))
      (node (ref "R25") (pin "1") (pinfunction "1_1") (pintype "passive"))
    )
    (net (code "52") (name "Net-(LED24-DO)") (class "Default")
      (node (ref "LED24") (pin "1") (pinfunction "DO_1") (pintype "passive"))
      (node (ref "R26") (pin "2") (pinfunction "2_2") (pintype "passive"))
    )
    (net (code "53") (name "Net-(LED25-DI)") (class "Default")
      (node (ref "LED25") (pin "3") (pinfunction "DI_3") (pintype "passive"))
      (node (ref "R26") (pin "1") (pinfunction "1_1") (pintype "passive"))
    )
    (net (code "54") (name "Net-(LED25-DO)") (class "Default")
      (node (ref "LED25") (pin "1") (pinfunction "DO_1") (pintype "passive"))
      (node (ref "R27") (pin "2") (pinfunction "2_2") (pintype "passive"))
    )
    (net (code "55") (name "Net-(LED26-DI)") (class "Default")
      (node (ref "LED26") (pin "3") (pinfunction "DI_3") (pintype "passive"))
      (node (ref "R27") (pin "1") (pinfunction "1_1") (pintype "passive"))
    )
    (net (code "56") (name "Net-(LED27-DI)") (class "Default")
      (node (ref "LED27") (pin "3") (pinfunction "DI_3") (pintype "passive"))
      (node (ref "R22") (pin "1") (pinfunction "1_1") (pintype "passive"))
    )
    (net (code "57") (name "Net-(LED27-DO)") (class "Default")
      (node (ref "LED27") (pin "1") (pinfunction "DO_1") (pintype "passive"))
      (node (ref "R28") (pin "2") (pinfunction "2_2") (pintype "passive"))
    )
    (net (code "58") (name "Net-(LED28-DI)") (class "Default")
      (node (ref "LED28") (pin "3") (pinfunction "DI_3") (pintype "passive"))
      (node (ref "R28") (pin "1") (pinfunction "1_1") (pintype "passive"))
    )
    (net (code "59") (name "Net-(LED28-DO)") (class "Default")
      (node (ref "LED28") (pin "1") (pinfunction "DO_1") (pintype "passive"))
      (node (ref "R29") (pin "2") (pinfunction "2_2") (pintype "passive"))
    )
    (net (code "60") (name "Net-(LED29-DI)") (class "Default")
      (node (ref "LED29") (pin "3") (pinfunction "DI_3") (pintype "passive"))
      (node (ref "R29") (pin "1") (pinfunction "1_1") (pintype "passive"))
    )
    (net (code "61") (name "Net-(LED29-DO)") (class "Default")
      (node (ref "LED29") (pin "1") (pinfunction "DO_1") (pintype "passive"))
      (node (ref "R30") (pin "2") (pinfunction "2_2") (pintype "passive"))
    )
    (net (code "62") (name "Net-(LED30-DI)") (class "Default")
      (node (ref "LED30") (pin "3") (pinfunction "DI_3") (pintype "passive"))
      (node (ref "R30") (pin "1") (pinfunction "1_1") (pintype "passive"))
    )
    (net (code "63") (name "Net-(LED30-DO)") (class "Default")
      (node (ref "LED30") (pin "1") (pinfunction "DO_1") (pintype "passive"))
      (node (ref "R31") (pin "2") (pinfunction "2_2") (pintype "passive"))
    )
    (net (code "64") (name "Net-(LED31-DI)") (class "Default")
      (node (ref "LED31") (pin "3") (pinfunction "DI_3") (pintype "passive"))
      (node (ref "R31") (pin "1") (pinfunction "1_1") (pintype "passive"))
    )
    (net (code "65") (name "Net-(LED31-DO)") (class "Default")
      (node (ref "LED31") (pin "1") (pinfunction "DO_1") (pintype "passive"))
      (node (ref "R32") (pin "2") (pinfunction "2_2") (pintype "passive"))
    )
    (net (code "66") (name "Net-(LED32-DI)") (class "Default")
      (node (ref "LED32") (pin "3") (pinfunction "DI_3") (pintype "passive"))
      (node (ref "R32") (pin "1") (pinfunction "1_1") (pintype "passive"))
    )
    (net (code "67") (name "unconnected-(LED26-DO-Pad1)") (class "Default")
      (node (ref "LED26") (pin "1") (pinfunction "DO_1") (pintype "passive"))
    )
    (net (code "68") (name "unconnected-(LED32-DO-Pad1)") (class "Default")
      (node (ref "LED32") (pin "1") (pinfunction "DO_1") (pintype "passive"))
    )
    (net (code "69") (name "unconnected-(MH8-Pad0)") (class "Default")
      (node (ref "MH8") (pin "0") (pinfunction "0_0") (pintype "passive"))
    )
    (net (code "70") (name "unconnected-(MH9-Pad0)") (class "Default")
      (node (ref "MH9") (pin "0") (pinfunction "0_0") (pintype "passive"))
    )
  )
)
